# cobra-mlx90640-native-junctions.net
KiCad netlist of a schematic drawn in Altium Designer
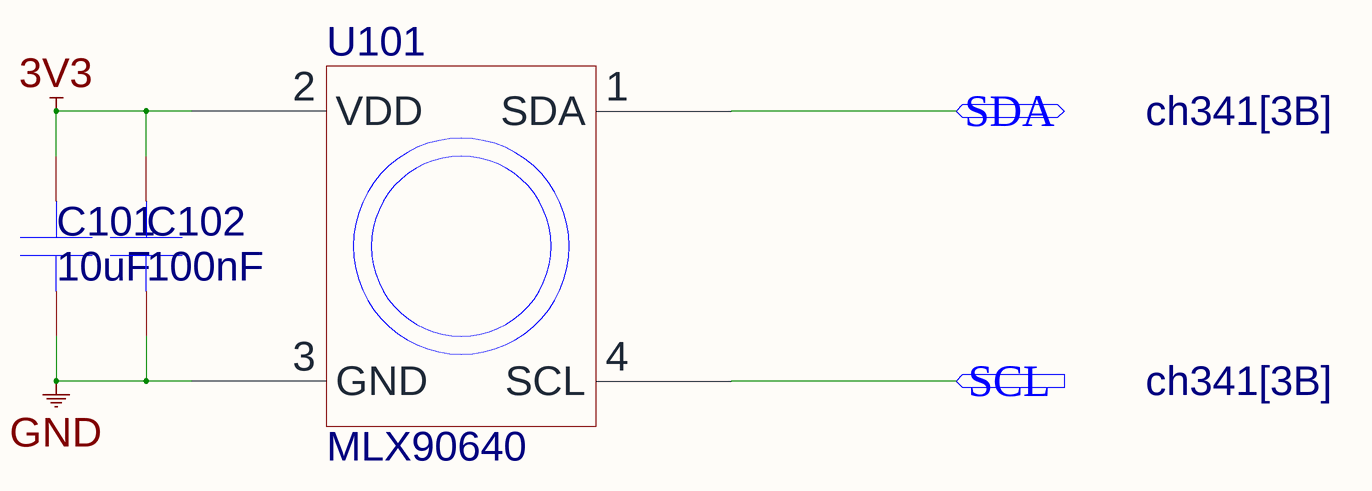
[diagram p0: cobra-mlx90640-native-junctions.SchDoc]

(export (version "E")
  (design (tool "Eeschema 10.0.6"))
  (components
    (comp (ref "C101") (value "10uF") (libsource (lib "altium-import") (part "root_0_SYM-0010_")))
    (comp (ref "C102") (value "100nF") (libsource (lib "") (part "root_0_SYM-0010__1")))
    (comp (ref "U101") (value "MLX90640") (libsource (lib "altium-import") (part "root_0_SYM-0017_")))
  )
  (nets
    (net (code "1") (name "/SCL") (class "Default")
      (node (ref "U101") (pin "4") (pinfunction "SCL_4") (pintype "passive"))
    )
    (net (code "2") (name "/SDA") (class "Default")
      (node (ref "U101") (pin "1") (pinfunction "SDA_1") (pintype "passive"))
    )
    (net (code "3") (name "3V3") (class "Default")
      (node (ref "C101") (pin "2") (pinfunction "2_2") (pintype "passive"))
      (node (ref "C102") (pin "2") (pinfunction "2_2") (pintype "passive"))
      (node (ref "U101") (pin "2") (pinfunction "VDD_2") (pintype "passive"))
    )
    (net (code "4") (name "GND") (class "Default")
      (node (ref "C101") (pin "1") (pinfunction "1_1") (pintype "passive"))
      (node (ref "C102") (pin "1") (pinfunction "1_1") (pintype "passive"))
      (node (ref "U101") (pin "3") (pinfunction "GND_3") (pintype "passive"))
    )
  )
)
